# Experiment1.net
KiCad netlist of a schematic drawn in EAGLE
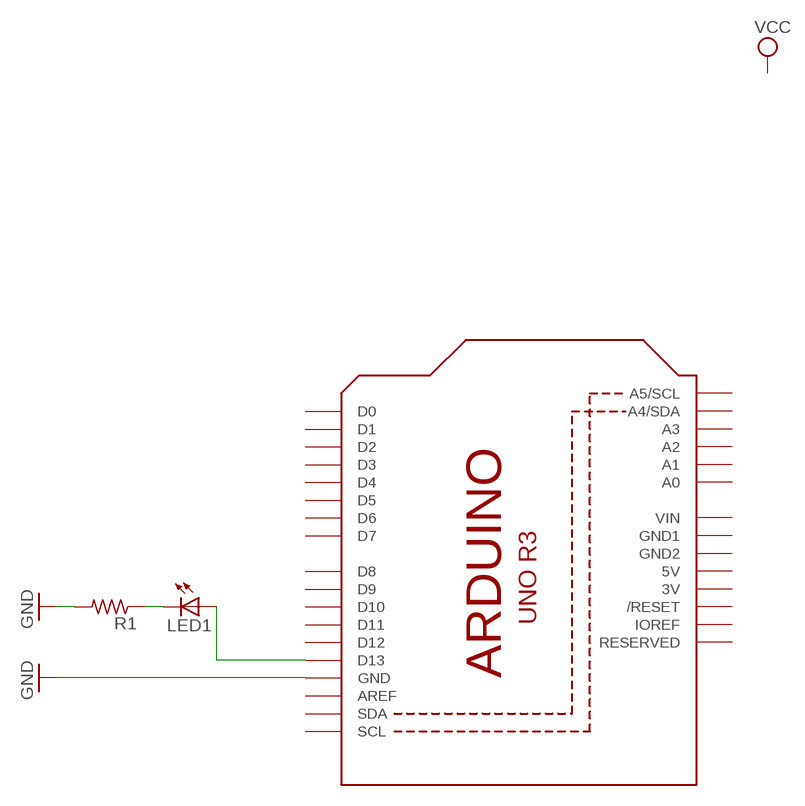
[diagram p0: schematic, sheet 1]

(export (version "E")
  (design (tool "Eeschema 10.0.6"))
  (components
    (comp (ref "LED1")
      (value "LED5MM")
      (footprint "eagle-import:LED5MM")
      (libsource (lib "eagle-import") (part "LED5MM"))
    )
    (comp (ref "R1")
      (value "R-US_0204/5")
      (footprint "eagle-import:0204_5")
      (libsource (lib "eagle-import") (part "R-US_0204/5"))
    )
    (comp (ref "U1")
      (value "ARDUINOR3-DIMENSION")
      (footprint "eagle-import:ARDUINOR3")
      (libsource (lib "eagle-import") (part "ARDUINOR3-DIMENSION"))
    )
  )
  (nets
    (net (code "1") (name "/3V") (class "Default")
      (node (ref "U1") (pin "3V") (pinfunction "3V_3V") (pintype "power_in"))
    )
    (net (code "2") (name "/5V") (class "Default")
      (node (ref "U1") (pin "5V") (pinfunction "5V_5V") (pintype "power_in"))
    )
    (net (code "3") (name "/GND1") (class "Default")
      (node (ref "U1") (pin "GND1") (pinfunction "GND1_GND1") (pintype "power_in"))
    )
    (net (code "4") (name "/GND2") (class "Default")
      (node (ref "U1") (pin "GND2") (pinfunction "GND2_GND2") (pintype "power_in"))
    )
    (net (code "5") (name "/VIN") (class "Default")
      (node (ref "U1") (pin "VIN") (pinfunction "VIN_VIN") (pintype "power_in"))
    )
    (net (code "6") (name "GND") (class "Default")
      (node (ref "R1") (pin "2") (pinfunction "2_2") (pintype "passive"))
      (node (ref "U1") (pin "GND") (pinfunction "GND_GND") (pintype "power_in"))
    )
    (net (code "7") (name "Net-(LED1-C)") (class "Default")
      (node (ref "LED1") (pin "K") (pinfunction "C_K") (pintype "passive"))
      (node (ref "R1") (pin "1") (pinfunction "1_1") (pintype "passive"))
    )
    (net (code "8") (name "Net-(LED1-PadA)") (class "Default")
      (node (ref "LED1") (pin "A") (pinfunction "A_A") (pintype "passive"))
      (node (ref "U1") (pin "D13") (pinfunction "D13_D13") (pintype "bidirectional"))
    )
    (net (code "10") (name "unconnected-(U1-A4{slash}SDA-PadA4)") (class "Default")
      (node (ref "U1") (pin "A4") (pinfunction "A4/SDA_A4") (pintype "bidirectional"))
    )
    (net (code "11") (name "unconnected-(U1-A5{slash}SCL-PadA5)") (class "Default")
      (node (ref "U1") (pin "A5") (pinfunction "A5/SCL_A5") (pintype "bidirectional"))
    )
    (net (code "12") (name "unconnected-(U1-PadA0)") (class "Default")
      (node (ref "U1") (pin "A0") (pinfunction "A0_A0") (pintype "bidirectional"))
    )
    (net (code "13") (name "unconnected-(U1-PadA1)") (class "Default")
      (node (ref "U1") (pin "A1") (pinfunction "A1_A1") (pintype "bidirectional"))
    )
    (net (code "14") (name "unconnected-(U1-PadA2)") (class "Default")
      (node (ref "U1") (pin "A2") (pinfunction "A2_A2") (pintype "bidirectional"))
    )
    (net (code "15") (name "unconnected-(U1-PadA3)") (class "Default")
      (node (ref "U1") (pin "A3") (pinfunction "A3_A3") (pintype "bidirectional"))
    )
    (net (code "16") (name "unconnected-(U1-PadAREF)") (class "Default")
      (node (ref "U1") (pin "AREF") (pinfunction "AREF_AREF") (pintype "bidirectional"))
    )
    (net (code "17") (name "unconnected-(U1-PadD0)") (class "Default")
      (node (ref "U1") (pin "D0") (pinfunction "D0_D0") (pintype "bidirectional"))
    )
    (net (code "18") (name "unconnected-(U1-PadD1)") (class "Default")
      (node (ref "U1") (pin "D1") (pinfunction "D1_D1") (pintype "bidirectional"))
    )
    (net (code "19") (name "unconnected-(U1-PadD2)") (class "Default")
      (node (ref "U1") (pin "D2") (pinfunction "D2_D2") (pintype "bidirectional"))
    )
    (net (code "20") (name "unconnected-(U1-PadD3)") (class "Default")
      (node (ref "U1") (pin "D3") (pinfunction "D3_D3") (pintype "bidirectional"))
    )
    (net (code "21") (name "unconnected-(U1-PadD4)") (class "Default")
      (node (ref "U1") (pin "D4") (pinfunction "D4_D4") (pintype "bidirectional"))
    )
    (net (code "22") (name "unconnected-(U1-PadD5)") (class "Default")
      (node (ref "U1") (pin "D5") (pinfunction "D5_D5") (pintype "bidirectional"))
    )
    (net (code "23") (name "unconnected-(U1-PadD6)") (class "Default")
      (node (ref "U1") (pin "D6") (pinfunction "D6_D6") (pintype "bidirectional"))
    )
    (net (code "24") (name "unconnected-(U1-PadD7)") (class "Default")
      (node (ref "U1") (pin "D7") (pinfunction "D7_D7") (pintype "bidirectional"))
    )
    (net (code "25") (name "unconnected-(U1-PadD8)") (class "Default")
      (node (ref "U1") (pin "D8") (pinfunction "D8_D8") (pintype "bidirectional"))
    )
    (net (code "26") (name "unconnected-(U1-PadD9)") (class "Default")
      (node (ref "U1") (pin "D9") (pinfunction "D9_D9") (pintype "bidirectional"))
    )
    (net (code "27") (name "unconnected-(U1-PadD10)") (class "Default")
      (node (ref "U1") (pin "D10") (pinfunction "D10_D10") (pintype "bidirectional"))
    )
    (net (code "28") (name "unconnected-(U1-PadD11)") (class "Default")
      (node (ref "U1") (pin "D11") (pinfunction "D11_D11") (pintype "bidirectional"))
    )
    (net (code "29") (name "unconnected-(U1-PadD12)") (class "Default")
      (node (ref "U1") (pin "D12") (pinfunction "D12_D12") (pintype "bidirectional"))
    )
    (net (code "30") (name "unconnected-(U1-PadIOREF)") (class "Default")
      (node (ref "U1") (pin "IOREF") (pinfunction "IOREF_IOREF") (pintype "output"))
    )
    (net (code "31") (name "unconnected-(U1-PadRESERVED)") (class "Default")
      (node (ref "U1") (pin "RESERVED") (pinfunction "RESERVED_RESERVED") (pintype "no_connect"))
    )
    (net (code "32") (name "unconnected-(U1-PadSCL)") (class "Default")
      (node (ref "U1") (pin "SCL") (pinfunction "SCL_SCL") (pintype "bidirectional"))
    )
    (net (code "33") (name "unconnected-(U1-PadSDA)") (class "Default")
      (node (ref "U1") (pin "SDA") (pinfunction "SDA_SDA") (pintype "bidirectional"))
    )
    (net (code "34") (name "unconnected-(U1-{slash}RESET-PadRESET)") (class "Default")
      (node (ref "U1") (pin "RESET") (pinfunction "/RESET_RESET") (pintype "bidirectional"))
    )
  )
)
